# test.net
KiCad netlist of a schematic drawn in EAGLE
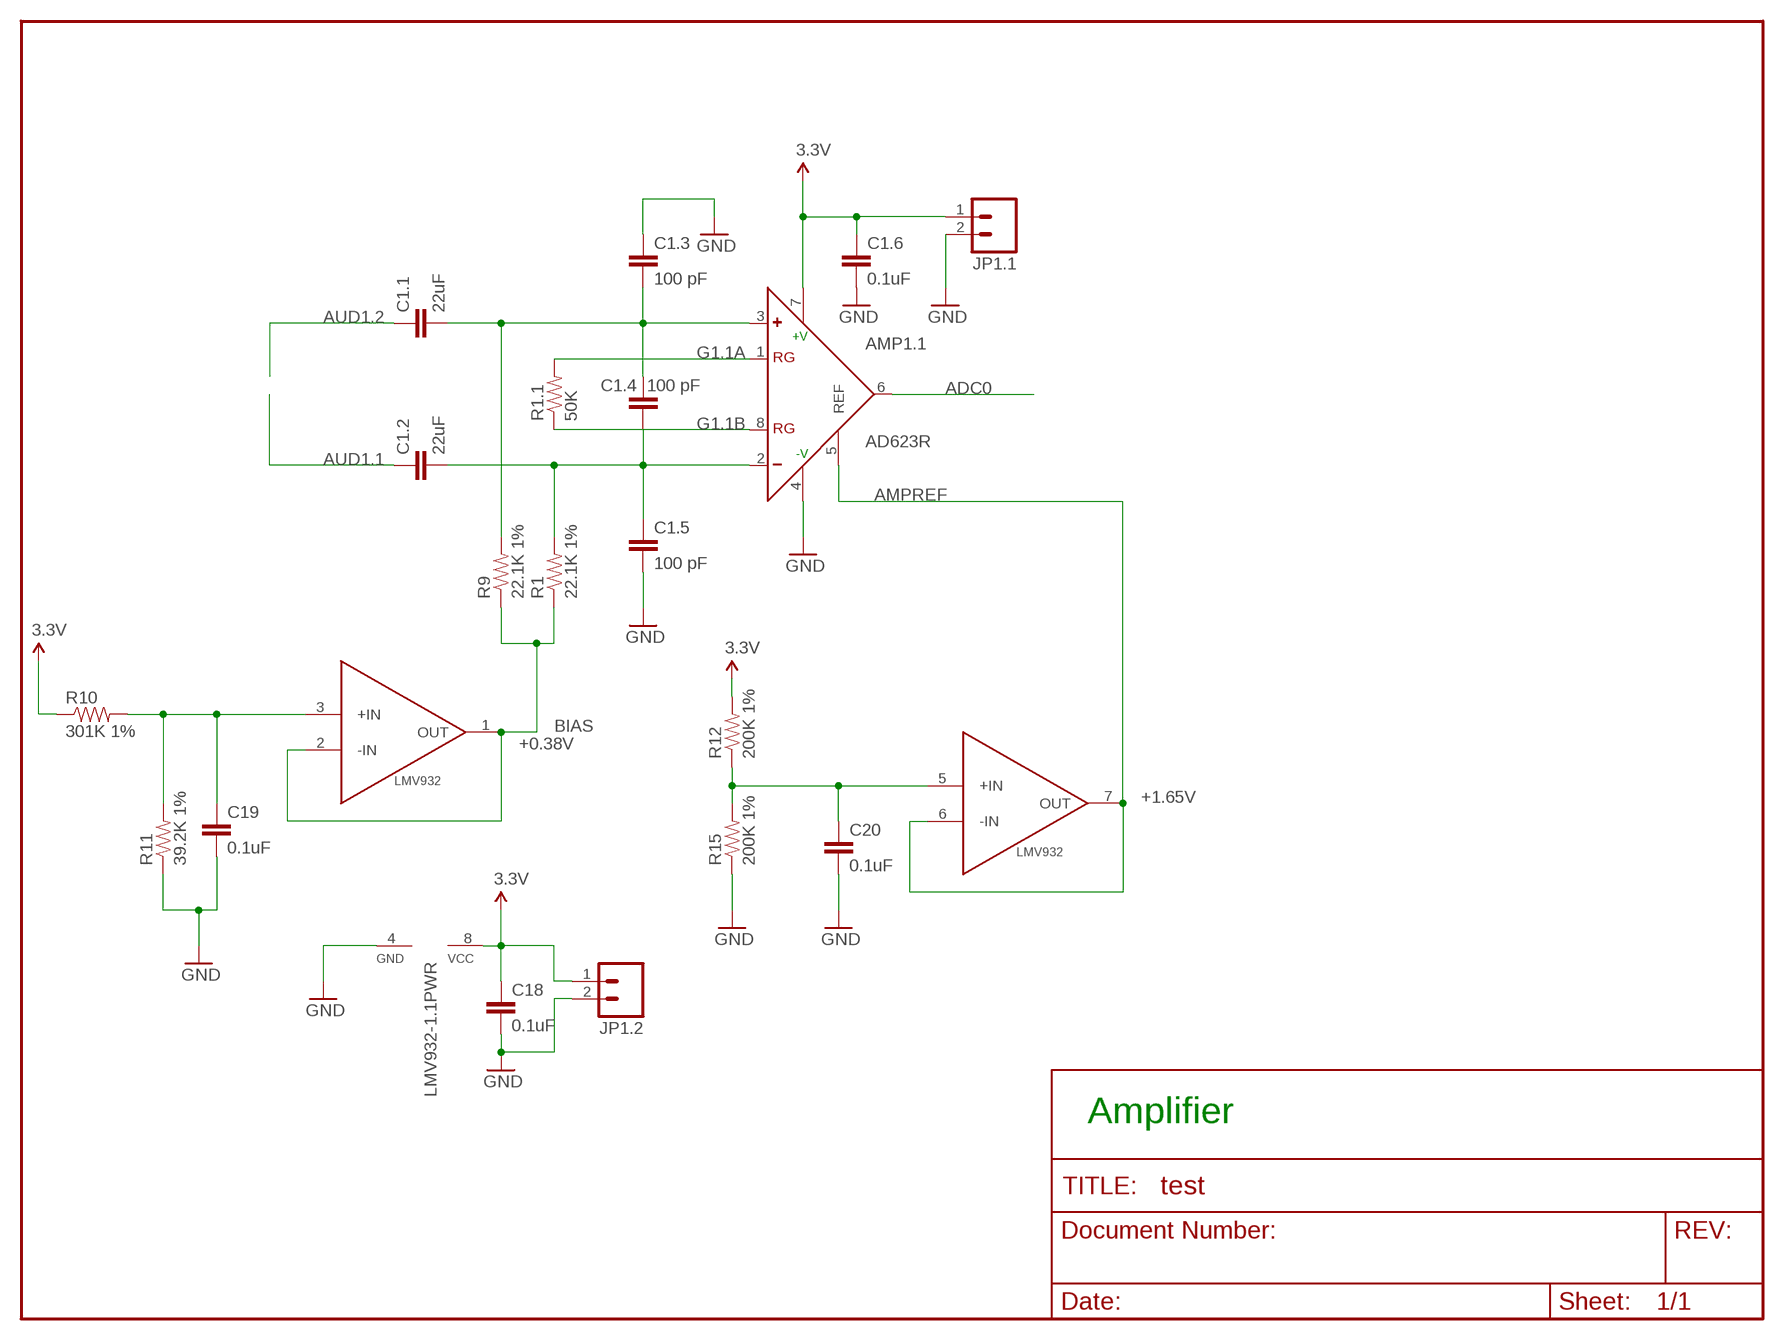
[diagram p0: schematic, sheet 1]

(export (version "E")
  (design (tool "Eeschema 10.0.6"))
  (components
    (comp (ref "AMP1.1")
      (value "AD623R")
      (footprint "eagle-import:SO8")
      (fields (field (name "MPN") "AD623ARZ."))
      (libsource (lib "eagle-import") (part "AD623R"))
    )
    (comp (ref "C1.1")
      (value "22uF")
      (footprint "eagle-import:1206")
      (libsource (lib "eagle-import") (part "CAP1206"))
    )
    (comp (ref "C1.2")
      (value "22uF")
      (footprint "eagle-import:1206")
      (libsource (lib "eagle-import") (part "CAP1206"))
    )
    (comp (ref "C1.3")
      (value "100 pF")
      (footprint "eagle-import:0805")
      (libsource (lib "eagle-import") (part "CAP0805"))
    )
    (comp (ref "C1.4")
      (value "100 pF")
      (footprint "eagle-import:0805")
      (libsource (lib "eagle-import") (part "CAP0805"))
    )
    (comp (ref "C1.5")
      (value "100 pF")
      (footprint "eagle-import:0805")
      (libsource (lib "eagle-import") (part "CAP0805"))
    )
    (comp (ref "C1.6")
      (value "0.1uF")
      (footprint "eagle-import:0805")
      (libsource (lib "eagle-import") (part "CAP0805"))
    )
    (comp (ref "C18")
      (value "0.1uF")
      (footprint "eagle-import:0805")
      (libsource (lib "eagle-import") (part "CAP0805"))
    )
    (comp (ref "C19")
      (value "0.1uF")
      (footprint "eagle-import:0805")
      (libsource (lib "eagle-import") (part "CAP0805"))
    )
    (comp (ref "C20")
      (value "0.1uF")
      (footprint "eagle-import:0805")
      (libsource (lib "eagle-import") (part "CAP0805"))
    )
    (comp (ref "JP1.1")
      (value "M021X02_NO_SILK")
      (footprint "eagle-import:1X02_NO_SILK")
      (libsource (lib "eagle-import") (part "M021X02_NO_SILK"))
    )
    (comp (ref "JP1.2")
      (value "M021X02_NO_SILK")
      (footprint "eagle-import:1X02_NO_SILK")
      (libsource (lib "eagle-import") (part "M021X02_NO_SILK"))
    )
    (comp (ref "LMV932-1.1")
      (value "LMV932")
      (footprint "eagle-import:SOIC8")
      (libsource (lib "eagle-import") (part "LMV932"))
    )
    (comp (ref "R1")
      (value "22.1K 1%")
      (footprint "eagle-import:0805")
      (libsource (lib "eagle-import") (part "RESISTOR0805-RES"))
    )
    (comp (ref "R1.1")
      (value "50K")
      (footprint "eagle-import:0805")
      (libsource (lib "eagle-import") (part "SparkFun-Passives_RESISTOR0805-RES"))
    )
    (comp (ref "R9")
      (value "22.1K 1%")
      (footprint "eagle-import:0805")
      (libsource (lib "eagle-import") (part "RESISTOR0805-RES"))
    )
    (comp (ref "R10")
      (value "301K 1%")
      (footprint "eagle-import:0805")
      (libsource (lib "eagle-import") (part "RESISTOR0805-RES"))
    )
    (comp (ref "R11")
      (value "39.2K 1%")
      (footprint "eagle-import:0805")
      (libsource (lib "eagle-import") (part "RESISTOR0805-RES"))
    )
    (comp (ref "R12")
      (value "200K 1%")
      (footprint "eagle-import:0805")
      (libsource (lib "eagle-import") (part "RESISTOR0805-RES"))
    )
    (comp (ref "R15")
      (value "200K 1%")
      (footprint "eagle-import:0805")
      (libsource (lib "eagle-import") (part "RESISTOR0805-RES"))
    )
  )
  (nets
    (net (code "1") (name "/ADC0") (class "Default")
      (node (ref "AMP1.1") (pin "6") (pinfunction "OUT_6") (pintype "output"))
    )
    (net (code "2") (name "/AMPREF") (class "Default")
      (node (ref "AMP1.1") (pin "5") (pinfunction "REF_5") (pintype "passive"))
      (node (ref "LMV932-1.1") (pin "6") (pinfunction "-IN_6") (pintype "input"))
      (node (ref "LMV932-1.1") (pin "7") (pinfunction "OUT_7") (pintype "output"))
    )
    (net (code "3") (name "/AUD1.1") (class "Default")
      (node (ref "C1.2") (pin "1") (pinfunction "1_1") (pintype "passive"))
    )
    (net (code "4") (name "/AUD1.2") (class "Default")
      (node (ref "C1.1") (pin "1") (pinfunction "1_1") (pintype "passive"))
    )
    (net (code "5") (name "/BIAS") (class "Default")
      (node (ref "LMV932-1.1") (pin "1") (pinfunction "OUT_1") (pintype "output"))
      (node (ref "LMV932-1.1") (pin "2") (pinfunction "-IN_2") (pintype "input"))
      (node (ref "R1") (pin "1") (pinfunction "1_1") (pintype "passive"))
      (node (ref "R9") (pin "1") (pinfunction "1_1") (pintype "passive"))
    )
    (net (code "6") (name "/G1.1A") (class "Default")
      (node (ref "AMP1.1") (pin "1") (pinfunction "RG_1") (pintype "passive"))
      (node (ref "R1.1") (pin "2") (pinfunction "2_2") (pintype "passive"))
    )
    (net (code "7") (name "/G1.1B") (class "Default")
      (node (ref "AMP1.1") (pin "8") (pinfunction "RG_8") (pintype "passive"))
      (node (ref "R1.1") (pin "1") (pinfunction "1_1") (pintype "passive"))
    )
    (net (code "8") (name "3.3V") (class "Default")
      (node (ref "AMP1.1") (pin "7") (pinfunction "+V_7") (pintype "power_in"))
      (node (ref "C1.6") (pin "1") (pinfunction "1_1") (pintype "passive"))
      (node (ref "C18") (pin "1") (pinfunction "1_1") (pintype "passive"))
      (node (ref "JP1.1") (pin "1") (pinfunction "1_1") (pintype "passive"))
      (node (ref "JP1.2") (pin "1") (pinfunction "1_1") (pintype "passive"))
      (node (ref "LMV932-1.1") (pin "8") (pinfunction "VCC_8") (pintype "power_in"))
      (node (ref "R10") (pin "1") (pinfunction "1_1") (pintype "passive"))
      (node (ref "R12") (pin "2") (pinfunction "2_2") (pintype "passive"))
    )
    (net (code "9") (name "GND") (class "Default")
      (node (ref "AMP1.1") (pin "4") (pinfunction "-V_4") (pintype "power_in"))
      (node (ref "C1.3") (pin "1") (pinfunction "1_1") (pintype "passive"))
      (node (ref "C1.5") (pin "2") (pinfunction "2_2") (pintype "passive"))
      (node (ref "C1.6") (pin "2") (pinfunction "2_2") (pintype "passive"))
      (node (ref "C18") (pin "2") (pinfunction "2_2") (pintype "passive"))
      (node (ref "C19") (pin "2") (pinfunction "2_2") (pintype "passive"))
      (node (ref "C20") (pin "2") (pinfunction "2_2") (pintype "passive"))
      (node (ref "JP1.1") (pin "2") (pinfunction "2_2") (pintype "passive"))
      (node (ref "JP1.2") (pin "2") (pinfunction "2_2") (pintype "passive"))
      (node (ref "LMV932-1.1") (pin "4") (pinfunction "GND_4") (pintype "power_in"))
      (node (ref "R11") (pin "1") (pinfunction "1_1") (pintype "passive"))
      (node (ref "R15") (pin "1") (pinfunction "1_1") (pintype "passive"))
    )
    (net (code "10") (name "Net-(AMP1.1-+)") (class "Default")
      (node (ref "AMP1.1") (pin "3") (pinfunction "+_3") (pintype "input"))
      (node (ref "C1.1") (pin "2") (pinfunction "2_2") (pintype "passive"))
      (node (ref "C1.3") (pin "2") (pinfunction "2_2") (pintype "passive"))
      (node (ref "C1.4") (pin "1") (pinfunction "1_1") (pintype "passive"))
      (node (ref "R9") (pin "2") (pinfunction "2_2") (pintype "passive"))
    )
    (net (code "11") (name "Net-(AMP1.1--)") (class "Default")
      (node (ref "AMP1.1") (pin "2") (pinfunction "-_2") (pintype "input"))
      (node (ref "C1.2") (pin "2") (pinfunction "2_2") (pintype "passive"))
      (node (ref "C1.4") (pin "2") (pinfunction "2_2") (pintype "passive"))
      (node (ref "C1.5") (pin "1") (pinfunction "1_1") (pintype "passive"))
      (node (ref "R1") (pin "2") (pinfunction "2_2") (pintype "passive"))
    )
    (net (code "12") (name "Net-(LMV932-1.1A-+IN)") (class "Default")
      (node (ref "C19") (pin "1") (pinfunction "1_1") (pintype "passive"))
      (node (ref "LMV932-1.1") (pin "3") (pinfunction "+IN_3") (pintype "input"))
      (node (ref "R10") (pin "2") (pinfunction "2_2") (pintype "passive"))
      (node (ref "R11") (pin "2") (pinfunction "2_2") (pintype "passive"))
    )
    (net (code "13") (name "Net-(LMV932-1.1B-+IN)") (class "Default")
      (node (ref "C20") (pin "1") (pinfunction "1_1") (pintype "passive"))
      (node (ref "LMV932-1.1") (pin "5") (pinfunction "+IN_5") (pintype "input"))
      (node (ref "R12") (pin "1") (pinfunction "1_1") (pintype "passive"))
      (node (ref "R15") (pin "2") (pinfunction "2_2") (pintype "passive"))
    )
  )
)
